# CP2104_USB_to_UART.net
KiCad netlist of a schematic drawn in EAGLE
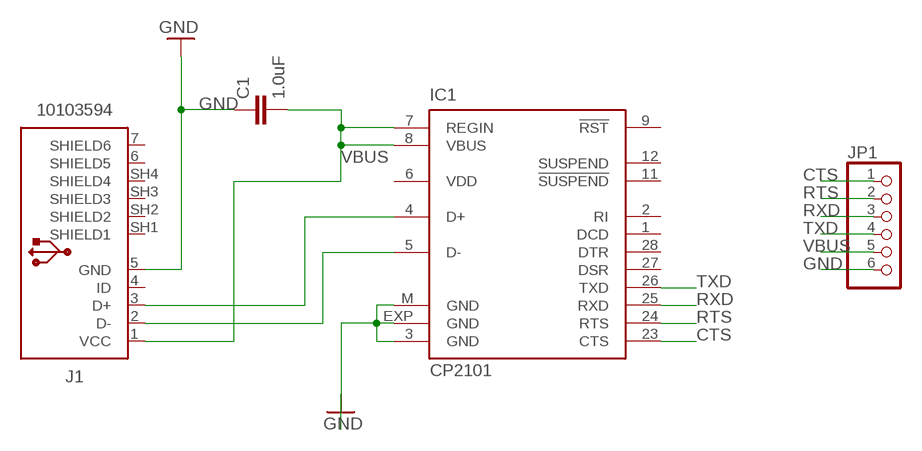
[diagram p0: schematic, sheet 1]

(export (version "E")
  (design (tool "Eeschema 10.0.6"))
  (components
    (comp (ref "C1")
      (value "1.0uF")
      (footprint "eagle-import:0805")
      (libsource (lib "eagle-import") (part "1.0UF-0805-25V-(+80/-20%)"))
    )
    (comp (ref "IC1")
      (value "CP2101")
      (footprint "eagle-import:MLP28")
      (fields (field (name "MF") "FARNELL") (field (name "MPN") "CP2102-GM"))
      (libsource (lib "eagle-import") (part "CP2101"))
    )
    (comp (ref "J1")
      (value "10103594")
      (footprint "eagle-import:10103594")
      (fields (field (name "MANUFACTURER") "Amphenol ICC (FCI)") (field (name "MPN") "10103594-0001LF"))
      (libsource (lib "eagle-import") (part "10103594"))
    )
    (comp (ref "JP1")
      (value "PINHD-1X6")
      (footprint "eagle-import:1X06")
      (libsource (lib "eagle-import") (part "PINHD-1X6"))
    )
  )
  (nets
    (net (code "1") (name "/CTS") (class "Default")
      (node (ref "IC1") (pin "23") (pinfunction "CTS_23") (pintype "input"))
      (node (ref "JP1") (pin "1") (pinfunction "1_1") (pintype "passive"))
    )
    (net (code "2") (name "/RTS") (class "Default")
      (node (ref "IC1") (pin "24") (pinfunction "RTS_24") (pintype "output"))
      (node (ref "JP1") (pin "2") (pinfunction "2_2") (pintype "passive"))
    )
    (net (code "3") (name "/RXD") (class "Default")
      (node (ref "IC1") (pin "25") (pinfunction "RXD_25") (pintype "input"))
      (node (ref "JP1") (pin "3") (pinfunction "3_3") (pintype "passive"))
    )
    (net (code "4") (name "/SHIELD1") (class "Default")
      (node (ref "J1") (pin "SH1") (pinfunction "SHIELD1_SH1") (pintype "power_in"))
    )
    (net (code "5") (name "/SHIELD2") (class "Default")
      (node (ref "J1") (pin "SH2") (pinfunction "SHIELD2_SH2") (pintype "power_in"))
    )
    (net (code "6") (name "/SHIELD3") (class "Default")
      (node (ref "J1") (pin "SH3") (pinfunction "SHIELD3_SH3") (pintype "power_in"))
    )
    (net (code "7") (name "/SHIELD4") (class "Default")
      (node (ref "J1") (pin "SH4") (pinfunction "SHIELD4_SH4") (pintype "power_in"))
    )
    (net (code "8") (name "/SHIELD5") (class "Default")
      (node (ref "J1") (pin "6") (pinfunction "SHIELD5_6") (pintype "power_in"))
    )
    (net (code "9") (name "/SHIELD6") (class "Default")
      (node (ref "J1") (pin "7") (pinfunction "SHIELD6_7") (pintype "power_in"))
    )
    (net (code "10") (name "/TXD") (class "Default")
      (node (ref "IC1") (pin "26") (pinfunction "TXD_26") (pintype "output"))
      (node (ref "JP1") (pin "4") (pinfunction "4_4") (pintype "passive"))
    )
    (net (code "11") (name "/VBUS") (class "Default")
      (node (ref "C1") (pin "2") (pinfunction "2_2") (pintype "passive"))
      (node (ref "IC1") (pin "7") (pinfunction "REGIN_7") (pintype "passive"))
      (node (ref "IC1") (pin "8") (pinfunction "VBUS_8") (pintype "input"))
      (node (ref "J1") (pin "1") (pinfunction "VCC_1") (pintype "power_in"))
      (node (ref "JP1") (pin "5") (pinfunction "5_5") (pintype "passive"))
    )
    (net (code "12") (name "/VDD") (class "Default")
      (node (ref "IC1") (pin "6") (pinfunction "VDD_6") (pintype "power_in"))
    )
    (net (code "13") (name "GND") (class "Default")
      (node (ref "C1") (pin "1") (pinfunction "1_1") (pintype "passive"))
      (node (ref "IC1") (pin "3") (pinfunction "GND_3") (pintype "power_in"))
      (node (ref "IC1") (pin "EXP") (pinfunction "GND_EXP") (pintype "power_in"))
      (node (ref "IC1") (pin "M") (pinfunction "GND_M") (pintype "power_in"))
      (node (ref "J1") (pin "5") (pinfunction "GND_5") (pintype "power_in"))
      (node (ref "JP1") (pin "6") (pinfunction "6_6") (pintype "passive"))
    )
    (net (code "14") (name "Net-(IC1-D+)") (class "Default")
      (node (ref "IC1") (pin "4") (pinfunction "D+_4") (pintype "bidirectional"))
      (node (ref "J1") (pin "3") (pinfunction "D+_3") (pintype "bidirectional"))
    )
    (net (code "15") (name "Net-(IC1-D-)") (class "Default")
      (node (ref "IC1") (pin "5") (pinfunction "D-_5") (pintype "bidirectional"))
      (node (ref "J1") (pin "2") (pinfunction "D-_2") (pintype "bidirectional"))
    )
    (net (code "16") (name "unconnected-(IC1-DCD-Pad1)") (class "Default")
      (node (ref "IC1") (pin "1") (pinfunction "DCD_1") (pintype "input"))
    )
    (net (code "17") (name "unconnected-(IC1-DSR-Pad27)") (class "Default")
      (node (ref "IC1") (pin "27") (pinfunction "DSR_27") (pintype "input"))
    )
    (net (code "18") (name "unconnected-(IC1-DTR-Pad28)") (class "Default")
      (node (ref "IC1") (pin "28") (pinfunction "DTR_28") (pintype "output"))
    )
    (net (code "19") (name "unconnected-(IC1-RI-Pad2)") (class "Default")
      (node (ref "IC1") (pin "2") (pinfunction "RI_2") (pintype "input"))
    )
    (net (code "20") (name "unconnected-(IC1-SUSPEND-Pad12)") (class "Default")
      (node (ref "IC1") (pin "12") (pinfunction "SUSPEND_12") (pintype "output"))
    )
    (net (code "21") (name "unconnected-(IC1-~{RST}-Pad9)") (class "Default")
      (node (ref "IC1") (pin "9") (pinfunction "~{RST}_9") (pintype "bidirectional"))
    )
    (net (code "22") (name "unconnected-(IC1-~{SUSPEND}-Pad11)") (class "Default")
      (node (ref "IC1") (pin "11") (pinfunction "~{SUSPEND}_11") (pintype "output"))
    )
    (net (code "23") (name "unconnected-(J1-ID-Pad4)") (class "Default")
      (node (ref "J1") (pin "4") (pinfunction "ID_4") (pintype "bidirectional"))
    )
  )
)
